# BQ76920_Protoboard_2.net
KiCad netlist of a schematic drawn in EAGLE
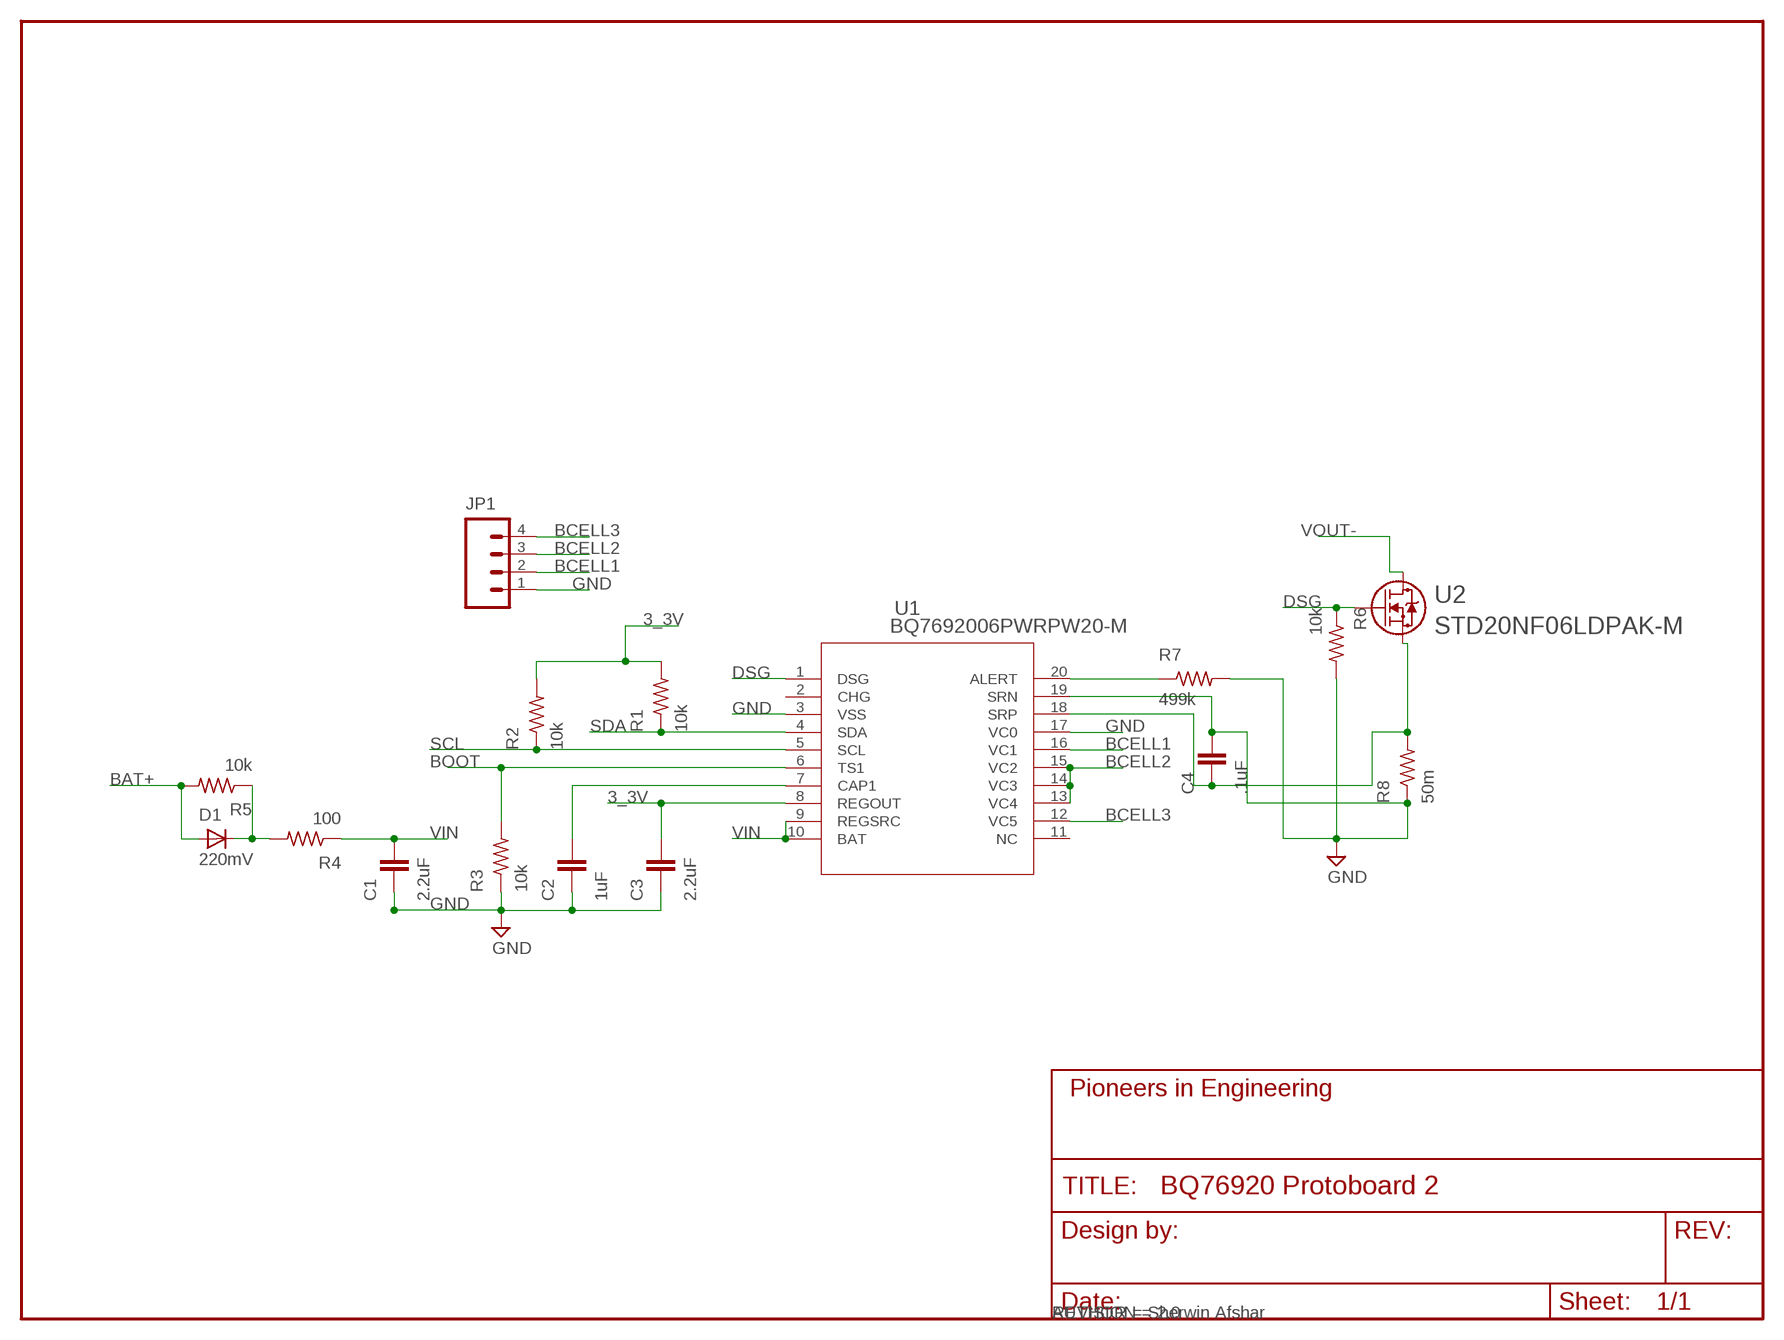
[diagram p0: schematic, sheet 1]

(export (version "E")
  (design (tool "Eeschema 10.0.6"))
  (components
    (comp (ref "C1")
      (value "2.2uF")
      (footprint "eagle-import:0603-CAP")
      (libsource (lib "eagle-import") (part "CAP0603-CAP"))
    )
    (comp (ref "C2")
      (value "1uF")
      (footprint "eagle-import:0603-CAP")
      (libsource (lib "eagle-import") (part "CAP0603-CAP"))
    )
    (comp (ref "C3")
      (value "2.2uF")
      (footprint "eagle-import:0603-CAP")
      (libsource (lib "eagle-import") (part "CAP0603-CAP"))
    )
    (comp (ref "C4")
      (value ".1uF")
      (footprint "eagle-import:0603-CAP")
      (libsource (lib "eagle-import") (part "CAP0603-CAP"))
    )
    (comp (ref "D1")
      (value "220mV")
      (footprint "eagle-import:SOD-323")
      (libsource (lib "eagle-import") (part "DIODESOD-323"))
    )
    (comp (ref "JP1")
      (value "M041X04-MTA")
      (footprint "eagle-import:1X04-MTA")
      (libsource (lib "eagle-import") (part "M041X04-MTA"))
    )
    (comp (ref "R1")
      (value "10k")
      (footprint "eagle-import:R0603")
      (fields (field (name "MANUFACTURER") "Rohm Semiconductor"))
      (libsource (lib "eagle-import") (part "R-US_R0603"))
    )
    (comp (ref "R2")
      (value "10k")
      (footprint "eagle-import:R0603")
      (fields (field (name "MANUFACTURER") "Rohm Semiconductor"))
      (libsource (lib "eagle-import") (part "R-US_R0603"))
    )
    (comp (ref "R3")
      (value "10k")
      (footprint "eagle-import:R0603")
      (fields (field (name "MANUFACTURER") "Rohm Semiconductor"))
      (libsource (lib "eagle-import") (part "R-US_R0603"))
    )
    (comp (ref "R4")
      (value "100")
      (footprint "eagle-import:R0603")
      (fields (field (name "MANUFACTURER") "Rohm Semiconductor"))
      (libsource (lib "eagle-import") (part "R-US_R0603"))
    )
    (comp (ref "R5")
      (value "10k")
      (footprint "eagle-import:R0603")
      (fields (field (name "MANUFACTURER") "Rohm Semiconductor"))
      (libsource (lib "eagle-import") (part "R-US_R0603"))
    )
    (comp (ref "R6")
      (value "10k")
      (footprint "eagle-import:R0603")
      (fields (field (name "MANUFACTURER") "Rohm Semiconductor"))
      (libsource (lib "eagle-import") (part "R-US_R0603"))
    )
    (comp (ref "R7")
      (value "499k")
      (footprint "eagle-import:R0603")
      (fields (field (name "MANUFACTURER") "Rohm Semiconductor"))
      (libsource (lib "eagle-import") (part "R-US_R0603"))
    )
    (comp (ref "R8")
      (value "50m")
      (footprint "eagle-import:R2512")
      (libsource (lib "eagle-import") (part "R-US_R2512"))
    )
    (comp (ref "U1")
      (value "BQ7692006PWRPW20-M")
      (footprint "eagle-import:PW20-M")
      (fields (field (name "MANUFACTURER_PART_NUMBER") "BQ7692006PWR"))
      (libsource (lib "eagle-import") (part "BQ7692006PWRPW20-M"))
    )
    (comp (ref "U2")
      (value "STD20NF06LDPAK-M")
      (footprint "eagle-import:DPAK-M")
      (fields (field (name "MANUFACTURER_PART_NUMBER") "STD20NF06L"))
      (libsource (lib "eagle-import") (part "STD20NF06LDPAK-M"))
    )
  )
  (nets
    (net (code "1") (name "/3_3V") (class "Default")
      (node (ref "C3") (pin "2") (pinfunction "2_2") (pintype "passive"))
      (node (ref "R1") (pin "2") (pinfunction "2_2") (pintype "passive"))
      (node (ref "R2") (pin "2") (pinfunction "2_2") (pintype "passive"))
      (node (ref "U1") (pin "8") (pinfunction "REGOUT_8") (pintype "power_in"))
    )
    (net (code "2") (name "/BAT+") (class "Default")
      (node (ref "D1") (pin "1") (pinfunction "A_1") (pintype "passive"))
      (node (ref "R5") (pin "2") (pinfunction "2_2") (pintype "passive"))
    )
    (net (code "3") (name "/BCELL1") (class "Default")
      (node (ref "JP1") (pin "2") (pinfunction "2_2") (pintype "passive"))
      (node (ref "U1") (pin "16") (pinfunction "VC1_16") (pintype "input"))
    )
    (net (code "4") (name "/BCELL2") (class "Default")
      (node (ref "JP1") (pin "3") (pinfunction "3_3") (pintype "passive"))
      (node (ref "U1") (pin "13") (pinfunction "VC4_13") (pintype "input"))
      (node (ref "U1") (pin "14") (pinfunction "VC3_14") (pintype "input"))
      (node (ref "U1") (pin "15") (pinfunction "VC2_15") (pintype "input"))
    )
    (net (code "5") (name "/BCELL3") (class "Default")
      (node (ref "JP1") (pin "4") (pinfunction "4_4") (pintype "passive"))
      (node (ref "U1") (pin "12") (pinfunction "VC5_12") (pintype "input"))
    )
    (net (code "6") (name "/BOOT") (class "Default")
      (node (ref "R3") (pin "2") (pinfunction "2_2") (pintype "passive"))
      (node (ref "U1") (pin "6") (pinfunction "TS1_6") (pintype "input"))
    )
    (net (code "7") (name "/DSG") (class "Default")
      (node (ref "R6") (pin "1") (pinfunction "1_1") (pintype "passive"))
      (node (ref "U1") (pin "1") (pinfunction "DSG_1") (pintype "output"))
      (node (ref "U2") (pin "1") (pinfunction "1_1") (pintype "passive"))
    )
    (net (code "8") (name "/SCL") (class "Default")
      (node (ref "R2") (pin "1") (pinfunction "1_1") (pintype "passive"))
      (node (ref "U1") (pin "5") (pinfunction "SCL_5") (pintype "input"))
    )
    (net (code "9") (name "/SDA") (class "Default")
      (node (ref "R1") (pin "1") (pinfunction "1_1") (pintype "passive"))
      (node (ref "U1") (pin "4") (pinfunction "SDA_4") (pintype "bidirectional"))
    )
    (net (code "10") (name "/VIN") (class "Default")
      (node (ref "C1") (pin "2") (pinfunction "2_2") (pintype "passive"))
      (node (ref "R4") (pin "1") (pinfunction "1_1") (pintype "passive"))
      (node (ref "U1") (pin "10") (pinfunction "BAT_10") (pintype "power_in"))
      (node (ref "U1") (pin "9") (pinfunction "REGSRC_9") (pintype "input"))
    )
    (net (code "11") (name "/VOUT-") (class "Default")
      (node (ref "U2") (pin "3") (pinfunction "2_3") (pintype "passive"))
    )
    (net (code "12") (name "GND") (class "Default")
      (node (ref "C1") (pin "1") (pinfunction "1_1") (pintype "passive"))
      (node (ref "C2") (pin "1") (pinfunction "1_1") (pintype "passive"))
      (node (ref "C3") (pin "1") (pinfunction "1_1") (pintype "passive"))
      (node (ref "C4") (pin "2") (pinfunction "2_2") (pintype "passive"))
      (node (ref "JP1") (pin "1") (pinfunction "1_1") (pintype "passive"))
      (node (ref "R3") (pin "1") (pinfunction "1_1") (pintype "passive"))
      (node (ref "R6") (pin "2") (pinfunction "2_2") (pintype "passive"))
      (node (ref "R7") (pin "2") (pinfunction "2_2") (pintype "passive"))
      (node (ref "R8") (pin "1") (pinfunction "1_1") (pintype "passive"))
      (node (ref "U1") (pin "17") (pinfunction "VC0_17") (pintype "input"))
      (node (ref "U1") (pin "19") (pinfunction "SRN_19") (pintype "input"))
      (node (ref "U1") (pin "3") (pinfunction "VSS_3") (pintype "power_in"))
    )
    (net (code "13") (name "Net-(D1-C)") (class "Default")
      (node (ref "D1") (pin "2") (pinfunction "C_2") (pintype "passive"))
      (node (ref "R4") (pin "2") (pinfunction "2_2") (pintype "passive"))
      (node (ref "R5") (pin "1") (pinfunction "1_1") (pintype "passive"))
    )
    (net (code "14") (name "Net-(U1-ALERT)") (class "Default")
      (node (ref "R7") (pin "1") (pinfunction "1_1") (pintype "passive"))
      (node (ref "U1") (pin "20") (pinfunction "ALERT_20") (pintype "bidirectional"))
    )
    (net (code "15") (name "Net-(U1-CAP1)") (class "Default")
      (node (ref "C2") (pin "2") (pinfunction "2_2") (pintype "passive"))
      (node (ref "U1") (pin "7") (pinfunction "CAP1_7") (pintype "output"))
    )
    (net (code "16") (name "Net-(U1-SRP)") (class "Default")
      (node (ref "C4") (pin "1") (pinfunction "1_1") (pintype "passive"))
      (node (ref "R8") (pin "2") (pinfunction "2_2") (pintype "passive"))
      (node (ref "U1") (pin "18") (pinfunction "SRP_18") (pintype "input"))
      (node (ref "U2") (pin "2") (pinfunction "3_2") (pintype "passive"))
    )
    (net (code "17") (name "unconnected-(U1-CHG-Pad2)") (class "Default")
      (node (ref "U1") (pin "2") (pinfunction "CHG_2") (pintype "output"))
    )
    (net (code "18") (name "unconnected-(U1-NC-Pad11)") (class "Default")
      (node (ref "U1") (pin "11") (pinfunction "NC_11") (pintype "no_connect"))
    )
  )
)
